# Power_subsystem.net
KiCad netlist of a schematic drawn in Altium Designer
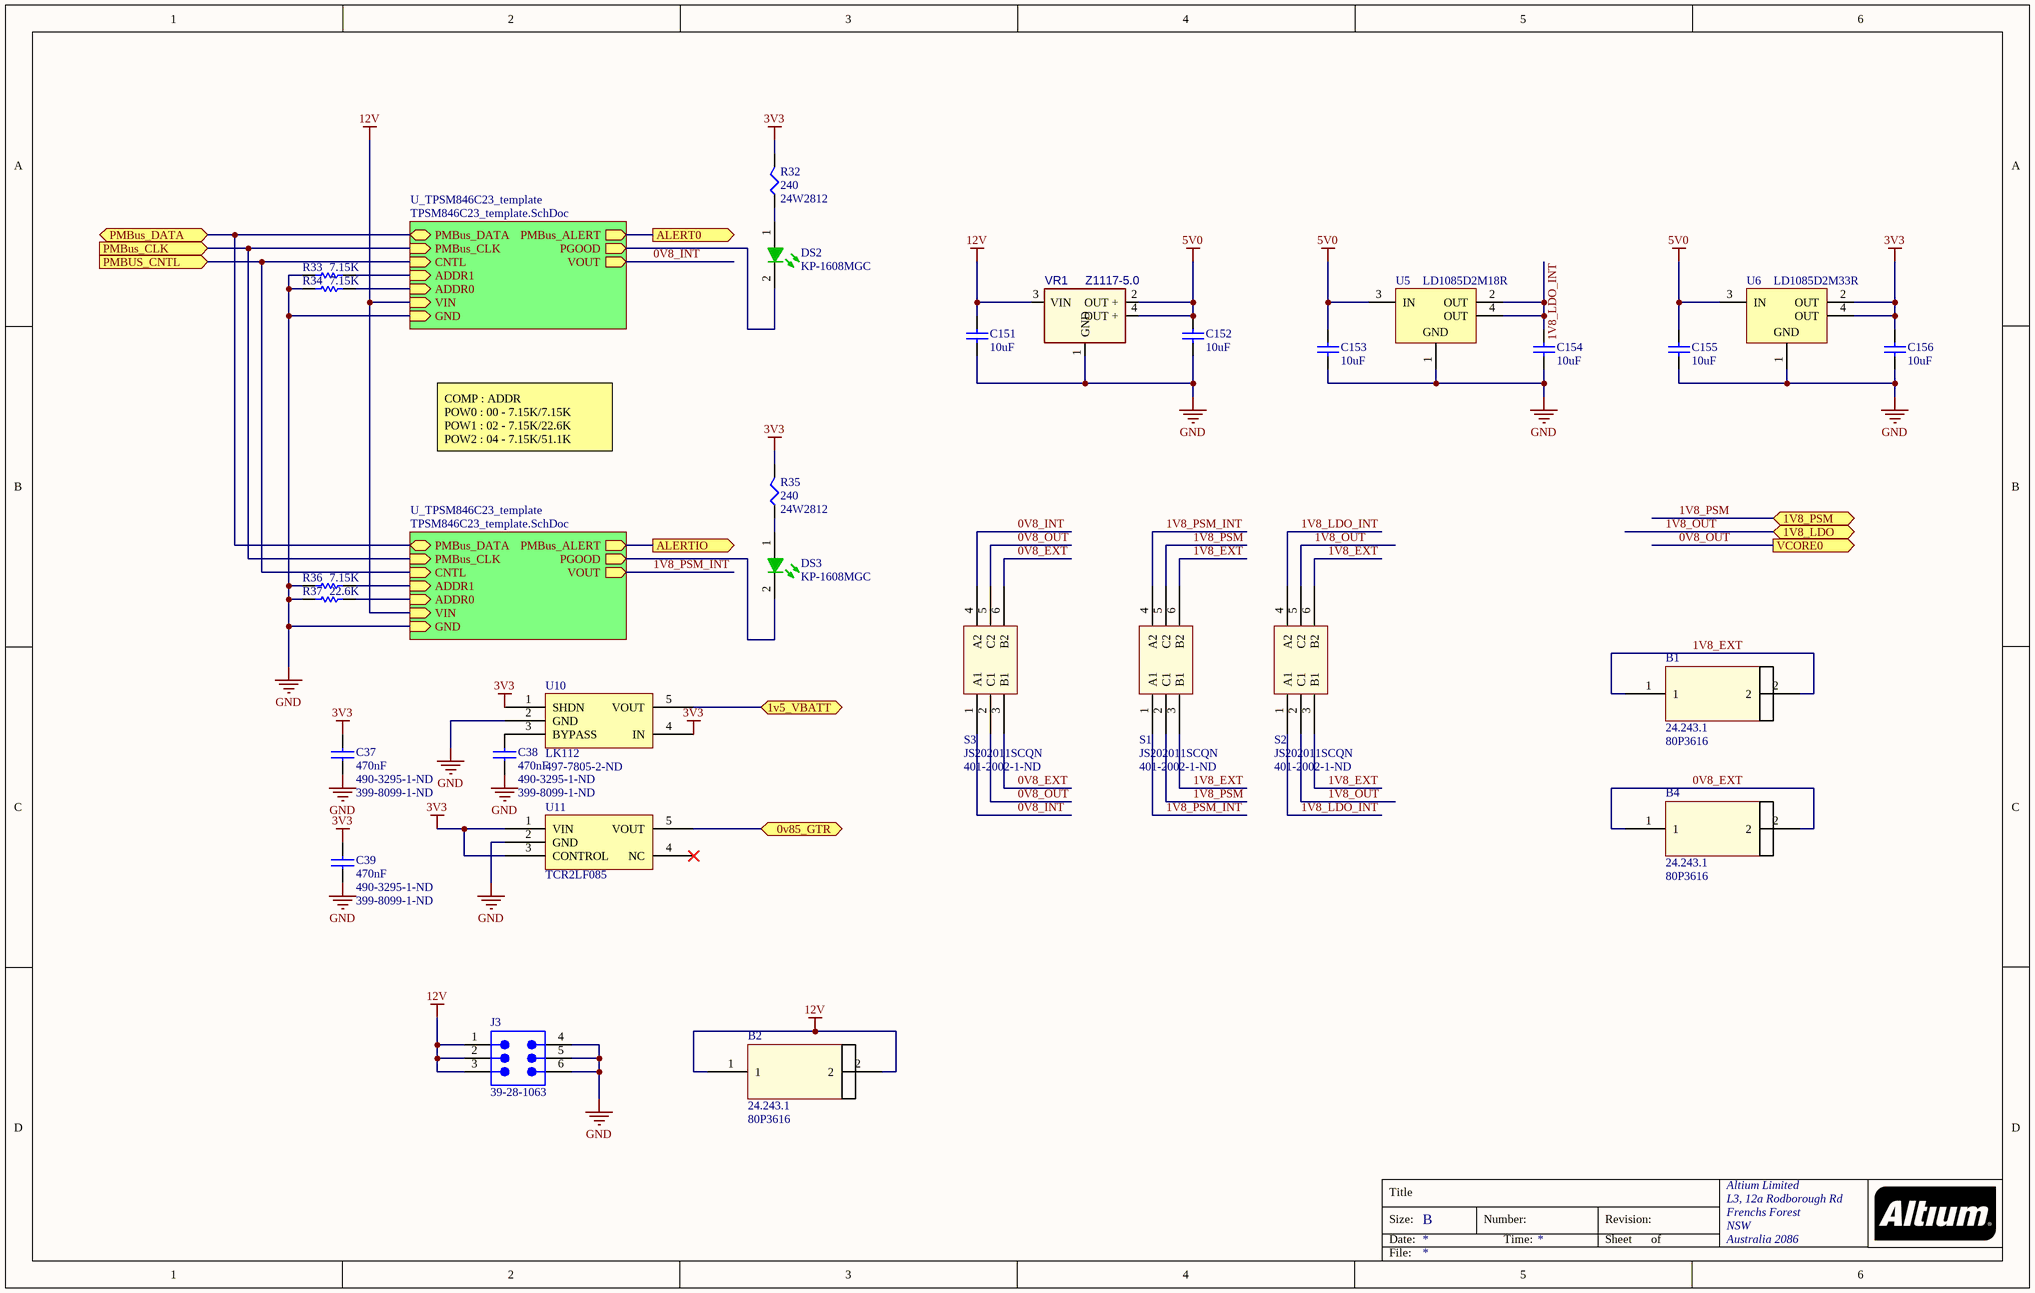
[diagram p0: Power_subsystem.SchDoc]

(export (version "E")
  (design (tool "Eeschema 10.0.6"))
  (components
    (comp (ref "B1")
      (value "24.243.1")
      (footprint "banana_clip")
      (fields (field (name "SUPPLIER PART NUMBER 1") "80P3616"))
      (libsource (lib "CGRA_schlib") (part "24.243.1"))
    )
    (comp (ref "B2")
      (value "24.243.1")
      (footprint "banana_clip")
      (fields (field (name "SUPPLIER PART NUMBER 1") "80P3616"))
      (libsource (lib "CGRA_schlib") (part "24.243.1"))
    )
    (comp (ref "B4")
      (value "24.243.1")
      (footprint "banana_clip")
      (fields (field (name "SUPPLIER PART NUMBER 1") "80P3616"))
      (libsource (lib "CGRA_schlib") (part "24.243.1"))
    )
    (comp (ref "C37")
      (value "CAP_470nF_1608mm_0603mil_1")
      (footprint "CAPC1005X06N")
      (description "0.47uF Capacitor")
      (fields
        (field (name "MANUFACTURER") "Murata")
        (field (name "MANUFACTURER PART NUMBER") "GRM155R61E225ME15D")
        (field (name "CAPACITANCE") "470nF")
        (field (name "SUPPLIER PART NUMBER 1") "490-3295-1-ND")
        (field (name "SUPPLIER PART NUMBER 2") "399-8099-1-ND")
      )
      (libsource (lib "CGRA_schlib") (part "CAP_470nF_1608mm_0603mil_1"))
    )
    (comp (ref "C38")
      (value "CAP_470nF_1608mm_0603mil_1")
      (footprint "CAPC1005X06N")
      (description "0.47uF Capacitor")
      (fields
        (field (name "MANUFACTURER") "Murata")
        (field (name "MANUFACTURER PART NUMBER") "GRM155R61E225ME15D")
        (field (name "CAPACITANCE") "470nF")
        (field (name "SUPPLIER PART NUMBER 1") "490-3295-1-ND")
        (field (name "SUPPLIER PART NUMBER 2") "399-8099-1-ND")
      )
      (libsource (lib "CGRA_schlib") (part "CAP_470nF_1608mm_0603mil_1"))
    )
    (comp (ref "C39")
      (value "CAP_470nF_1608mm_0603mil_1")
      (footprint "CAPC1005X06N")
      (description "0.47uF Capacitor")
      (fields
        (field (name "MANUFACTURER") "Murata")
        (field (name "MANUFACTURER PART NUMBER") "GRM155R61E225ME15D")
        (field (name "CAPACITANCE") "470nF")
        (field (name "SUPPLIER PART NUMBER 1") "490-3295-1-ND")
        (field (name "SUPPLIER PART NUMBER 2") "399-8099-1-ND")
      )
      (libsource (lib "CGRA_schlib") (part "CAP_470nF_1608mm_0603mil_1"))
    )
    (comp (ref "C151")
      (value "10uF")
      (footprint "CAPC0805(2012)145_N")
      (libsource (lib "my_schsymbols") (part "CAP_0805"))
    )
    (comp (ref "C152")
      (value "10uF")
      (footprint "CAPC0805(2012)145_N")
      (libsource (lib "my_schsymbols") (part "CAP_0805"))
    )
    (comp (ref "C153")
      (value "10uF")
      (footprint "CAPC0805(2012)145_N")
      (libsource (lib "my_schsymbols") (part "CAP_0805"))
    )
    (comp (ref "C154")
      (value "10uF")
      (footprint "CAPC0805(2012)145_N")
      (libsource (lib "my_schsymbols") (part "CAP_0805"))
    )
    (comp (ref "C155")
      (value "10uF")
      (footprint "CAPC0805(2012)145_N")
      (libsource (lib "my_schsymbols") (part "CAP_0805"))
    )
    (comp (ref "C156")
      (value "10uF")
      (footprint "CAPC0805(2012)145_N")
      (libsource (lib "my_schsymbols") (part "CAP_0805"))
    )
    (comp (ref "DS2")
      (value "KP-1608MGC")
      (footprint "KING-0603LED_GREEN_V")
      (description "LED, SMT, 0603(1608), 1.1mm thickness, Green")
      (fields (field (name "MANUFACTURER") "Kingbright"))
      (libsource (lib "Altium Content Vault") (part "KING-LED-GREEN-A1K2-2"))
    )
    (comp (ref "DS3")
      (value "KP-1608MGC")
      (footprint "KING-0603LED_GREEN_V")
      (description "LED, SMT, 0603(1608), 1.1mm thickness, Green")
      (fields (field (name "MANUFACTURER") "Kingbright"))
      (libsource (lib "Altium Content Vault") (part "KING-LED-GREEN-A1K2-2"))
    )
    (comp (ref "J3")
      (value "39-28-1063")
      (footprint "MOLX-39-28-1063_V")
      (libsource (lib "Altium Content Vault") (part "MOLX-39-28-1063"))
    )
    (comp (ref "R32")
      (value "RES_240_0603")
      (footprint "RESC1608X06N")
      (description "Res Thin Film 0603 240 Ohm 0.1% 0.1W(1/10W) ±25ppm/C Molded SMD Automotive Punched T/R")
      (fields
        (field (name "MANUFACTURER") "Panasonic")
        (field (name "MANUFACTURER PART NUMBER") "ERA-3AEB101V")
        (field (name "RESISTANCE") "240")
        (field (name "SUPPLIER PART NUMBER 1") "24W2812")
      )
      (libsource (lib "CGRA_schlib") (part "RES_240_0603"))
    )
    (comp (ref "R33")
      (value "7.15K")
      (footprint "RESC0402(1005)_N")
      (libsource (lib "my_schsymbols") (part "RES_0402"))
    )
    (comp (ref "R34")
      (value "7.15K")
      (footprint "RESC0402(1005)_N")
      (libsource (lib "my_schsymbols") (part "RES_0402"))
    )
    (comp (ref "R35")
      (value "RES_240_0603")
      (footprint "RESC1608X06N")
      (description "Res Thin Film 0603 240 Ohm 0.1% 0.1W(1/10W) ±25ppm/C Molded SMD Automotive Punched T/R")
      (fields
        (field (name "MANUFACTURER") "Panasonic")
        (field (name "MANUFACTURER PART NUMBER") "ERA-3AEB101V")
        (field (name "RESISTANCE") "240")
        (field (name "SUPPLIER PART NUMBER 1") "24W2812")
      )
      (libsource (lib "CGRA_schlib") (part "RES_240_0603"))
    )
    (comp (ref "R36")
      (value "7.15K")
      (footprint "RESC0402(1005)_N")
      (libsource (lib "my_schsymbols") (part "RES_0402"))
    )
    (comp (ref "R37")
      (value "22.6K")
      (footprint "RESC0402(1005)_N")
      (libsource (lib "my_schsymbols") (part "RES_0402"))
    )
    (comp (ref "S1")
      (value "JS202011SCQN")
      (footprint "JS202011SCQN_auto")
      (fields (field (name "SUPPLIER PART NUMBER 1") "401-2002-1-ND"))
      (libsource (lib "CGRA_schlib") (part "JS202011SCQN"))
    )
    (comp (ref "S2")
      (value "JS202011SCQN")
      (footprint "JS202011SCQN_auto")
      (fields (field (name "SUPPLIER PART NUMBER 1") "401-2002-1-ND"))
      (libsource (lib "CGRA_schlib") (part "JS202011SCQN"))
    )
    (comp (ref "S3")
      (value "JS202011SCQN")
      (footprint "JS202011SCQN_auto")
      (fields (field (name "SUPPLIER PART NUMBER 1") "401-2002-1-ND"))
      (libsource (lib "CGRA_schlib") (part "JS202011SCQN"))
    )
    (comp (ref "U5")
      (value "LD1085D2M18R")
      (footprint "D2PAK_A_M")
      (description "3A, Low Drop Positive Voltage Regulator, 1.8V, 4-Pin D2PAK/A")
      (libsource (lib "Altium Content Vault") (part "PM-REG-LD1085-SOT4"))
    )
    (comp (ref "U6")
      (value "LD1085D2M33R")
      (footprint "D2PAK_A_L")
      (description "3A, Low Drop Positive Voltage Regulator, 3.3V, 4-Pin D2PAK/A")
      (libsource (lib "Altium Content Vault") (part "PM-REG-LD1085-SOT4"))
    )
    (comp (ref "U10")
      (value "LK112")
      (footprint "SOT95P280X110-5N")
      (description "1.5V regulator")
      (fields (field (name "SUPPLIER PART NUMBER 1") "497-7805-2-ND"))
      (libsource (lib "CGRA_schlib") (part "LK112"))
    )
    (comp (ref "U11")
      (value "TCR2LF085")
      (footprint "SOT95P280X110-5N")
      (description "0.85V regulator")
      (libsource (lib "CGRA_schlib") (part "TCR2LF085"))
    )
    (comp (ref "VR1")
      (value "Z1117-5.0")
      (footprint "SOT-223")
      (description "IC REG LDO 1A SOT223-3")
      (fields
        (field (name "MFR PART NUMBER") "ZLDO1117G50TA")
        (field (name "MANUFACTURER") "Diodes")
        (field (name "CREATED BY") "murbach")
        (field (name "UPDATED BY") "User 3")
      )
      (libsource (lib "my_schsymbols") (part "ZLDO1117"))
    )
  )
  (nets
    (net (code "1") (name "/0V8_EXT") (class "Default")
      (node (ref "B4") (pin "1") (pinfunction "1_1") (pintype "passive"))
      (node (ref "B4") (pin "2") (pinfunction "2_2") (pintype "passive"))
      (node (ref "S3") (pin "3") (pinfunction "B1_3") (pintype "passive"))
      (node (ref "S3") (pin "6") (pinfunction "B2_6") (pintype "passive"))
    )
    (net (code "2") (name "/0V8_INT") (class "Default")
      (node (ref "S3") (pin "1") (pinfunction "A1_1") (pintype "passive"))
      (node (ref "S3") (pin "4") (pinfunction "A2_4") (pintype "passive"))
    )
    (net (code "3") (name "/0V8_OUT") (class "Default")
      (node (ref "S3") (pin "2") (pinfunction "C1_2") (pintype "passive"))
      (node (ref "S3") (pin "5") (pinfunction "C2_5") (pintype "passive"))
    )
    (net (code "4") (name "/0v85_GTR") (class "Default")
      (node (ref "U11") (pin "5") (pinfunction "VOUT_5") (pintype "passive"))
    )
    (net (code "5") (name "/1V8_EXT") (class "Default")
      (node (ref "B1") (pin "1") (pinfunction "1_1") (pintype "passive"))
      (node (ref "B1") (pin "2") (pinfunction "2_2") (pintype "passive"))
      (node (ref "S1") (pin "3") (pinfunction "B1_3") (pintype "passive"))
      (node (ref "S1") (pin "6") (pinfunction "B2_6") (pintype "passive"))
      (node (ref "S2") (pin "3") (pinfunction "B1_3") (pintype "passive"))
      (node (ref "S2") (pin "6") (pinfunction "B2_6") (pintype "passive"))
    )
    (net (code "6") (name "/1V8_LDO_INT") (class "Default")
      (node (ref "C154") (pin "2") (pinfunction "2_2") (pintype "passive"))
      (node (ref "S2") (pin "1") (pinfunction "A1_1") (pintype "passive"))
      (node (ref "S2") (pin "4") (pinfunction "A2_4") (pintype "passive"))
      (node (ref "U5") (pin "2") (pinfunction "OUT_2") (pintype "power_in"))
      (node (ref "U5") (pin "4") (pinfunction "OUT_4") (pintype "power_in"))
    )
    (net (code "7") (name "/1V8_OUT") (class "Default")
      (node (ref "S2") (pin "2") (pinfunction "C1_2") (pintype "passive"))
      (node (ref "S2") (pin "5") (pinfunction "C2_5") (pintype "passive"))
    )
    (net (code "8") (name "/1V8_PSM") (class "Default")
      (node (ref "S1") (pin "2") (pinfunction "C1_2") (pintype "passive"))
      (node (ref "S1") (pin "5") (pinfunction "C2_5") (pintype "passive"))
    )
    (net (code "9") (name "/1V8_PSM_INT") (class "Default")
      (node (ref "S1") (pin "1") (pinfunction "A1_1") (pintype "passive"))
      (node (ref "S1") (pin "4") (pinfunction "A2_4") (pintype "passive"))
    )
    (net (code "10") (name "/1v5_VBATT") (class "Default")
      (node (ref "U10") (pin "5") (pinfunction "VOUT_5") (pintype "passive"))
    )
    (net (code "11") (name "/ADDR0") (class "Default")
      (node (ref "R37") (pin "2") (pinfunction "2_2") (pintype "passive"))
    )
    (net (code "12") (name "/ADDR0_1") (class "Default")
      (node (ref "R34") (pin "2") (pinfunction "2_2") (pintype "passive"))
    )
    (net (code "13") (name "/ADDR1") (class "Default")
      (node (ref "R36") (pin "2") (pinfunction "2_2") (pintype "passive"))
    )
    (net (code "14") (name "/ADDR1_1") (class "Default")
      (node (ref "R33") (pin "2") (pinfunction "2_2") (pintype "passive"))
    )
    (net (code "17") (name "/PGOOD") (class "Default")
      (node (ref "DS3") (pin "2") (pinfunction "K_2") (pintype "passive"))
    )
    (net (code "18") (name "/PGOOD_1") (class "Default")
      (node (ref "DS2") (pin "2") (pinfunction "K_2") (pintype "passive"))
    )
    (net (code "22") (name "3V3") (class "Default")
      (node (ref "C156") (pin "2") (pinfunction "2_2") (pintype "passive"))
      (node (ref "C37") (pin "1") (pintype "passive"))
      (node (ref "C39") (pin "1") (pintype "passive"))
      (node (ref "R32") (pin "1") (pintype "passive"))
      (node (ref "R35") (pin "1") (pintype "passive"))
      (node (ref "U10") (pin "1") (pinfunction "SHDN_1") (pintype "passive"))
      (node (ref "U10") (pin "4") (pinfunction "IN_4") (pintype "passive"))
      (node (ref "U11") (pin "1") (pinfunction "VIN_1") (pintype "passive"))
      (node (ref "U11") (pin "3") (pinfunction "CONTROL_3") (pintype "passive"))
      (node (ref "U6") (pin "2") (pinfunction "OUT_2") (pintype "power_in"))
      (node (ref "U6") (pin "4") (pinfunction "OUT_4") (pintype "power_in"))
    )
    (net (code "23") (name "5V0") (class "Default")
      (node (ref "C152") (pin "2") (pinfunction "2_2") (pintype "passive"))
      (node (ref "C153") (pin "2") (pinfunction "2_2") (pintype "passive"))
      (node (ref "C155") (pin "2") (pinfunction "2_2") (pintype "passive"))
      (node (ref "U5") (pin "3") (pinfunction "IN_3") (pintype "power_in"))
      (node (ref "U6") (pin "3") (pinfunction "IN_3") (pintype "power_in"))
      (node (ref "VR1") (pin "2") (pinfunction "OUT_+_2") (pintype "passive"))
      (node (ref "VR1") (pin "4") (pinfunction "OUT_+_4") (pintype "passive"))
    )
    (net (code "24") (name "12V") (class "Default")
      (node (ref "B2") (pin "1") (pinfunction "1_1") (pintype "passive"))
      (node (ref "B2") (pin "2") (pinfunction "2_2") (pintype "passive"))
      (node (ref "C151") (pin "2") (pinfunction "2_2") (pintype "passive"))
      (node (ref "J3") (pin "1") (pinfunction "1_1") (pintype "passive"))
      (node (ref "J3") (pin "2") (pinfunction "2_2") (pintype "passive"))
      (node (ref "J3") (pin "3") (pinfunction "3_3") (pintype "passive"))
      (node (ref "VR1") (pin "3") (pinfunction "VIN_3") (pintype "passive"))
    )
    (net (code "25") (name "GND") (class "Default")
      (node (ref "C151") (pin "1") (pinfunction "1_1") (pintype "passive"))
      (node (ref "C152") (pin "1") (pinfunction "1_1") (pintype "passive"))
      (node (ref "C153") (pin "1") (pinfunction "1_1") (pintype "passive"))
      (node (ref "C154") (pin "1") (pinfunction "1_1") (pintype "passive"))
      (node (ref "C155") (pin "1") (pinfunction "1_1") (pintype "passive"))
      (node (ref "C156") (pin "1") (pinfunction "1_1") (pintype "passive"))
      (node (ref "C37") (pin "2") (pinfunction "2_2") (pintype "passive"))
      (node (ref "C38") (pin "2") (pinfunction "2_2") (pintype "passive"))
      (node (ref "C39") (pin "2") (pinfunction "2_2") (pintype "passive"))
      (node (ref "J3") (pin "4") (pinfunction "4_4") (pintype "passive"))
      (node (ref "J3") (pin "5") (pinfunction "5_5") (pintype "passive"))
      (node (ref "J3") (pin "6") (pinfunction "6_6") (pintype "passive"))
      (node (ref "R33") (pin "1") (pinfunction "1_1") (pintype "passive"))
      (node (ref "R34") (pin "1") (pinfunction "1_1") (pintype "passive"))
      (node (ref "R36") (pin "1") (pinfunction "1_1") (pintype "passive"))
      (node (ref "R37") (pin "1") (pinfunction "1_1") (pintype "passive"))
      (node (ref "U10") (pin "2") (pinfunction "GND_2") (pintype "passive"))
      (node (ref "U11") (pin "2") (pinfunction "GND_2") (pintype "passive"))
      (node (ref "U5") (pin "1") (pinfunction "GND_1") (pintype "power_in"))
      (node (ref "U6") (pin "1") (pinfunction "GND_1") (pintype "power_in"))
      (node (ref "VR1") (pin "1") (pinfunction "GND_1") (pintype "passive"))
    )
    (net (code "26") (name "Net-(DS2-A)") (class "Default")
      (node (ref "DS2") (pin "1") (pinfunction "A_1") (pintype "passive"))
      (node (ref "R32") (pin "2") (pinfunction "2_2") (pintype "passive"))
    )
    (net (code "27") (name "Net-(DS3-A)") (class "Default")
      (node (ref "DS3") (pin "1") (pinfunction "A_1") (pintype "passive"))
      (node (ref "R35") (pin "2") (pinfunction "2_2") (pintype "passive"))
    )
    (net (code "28") (name "Net-(U10-BYPASS)") (class "Default")
      (node (ref "C38") (pin "1") (pintype "passive"))
      (node (ref "U10") (pin "3") (pinfunction "BYPASS_3") (pintype "passive"))
    )
    (net (code "29") (name "unconnected-(U11-NC-Pad4)") (class "Default")
      (node (ref "U11") (pin "4") (pinfunction "NC_4") (pintype "passive+no_connect"))
    )
  )
)
